# UPX_Port_Adapter.net
KiCad netlist of a schematic drawn in EAGLE
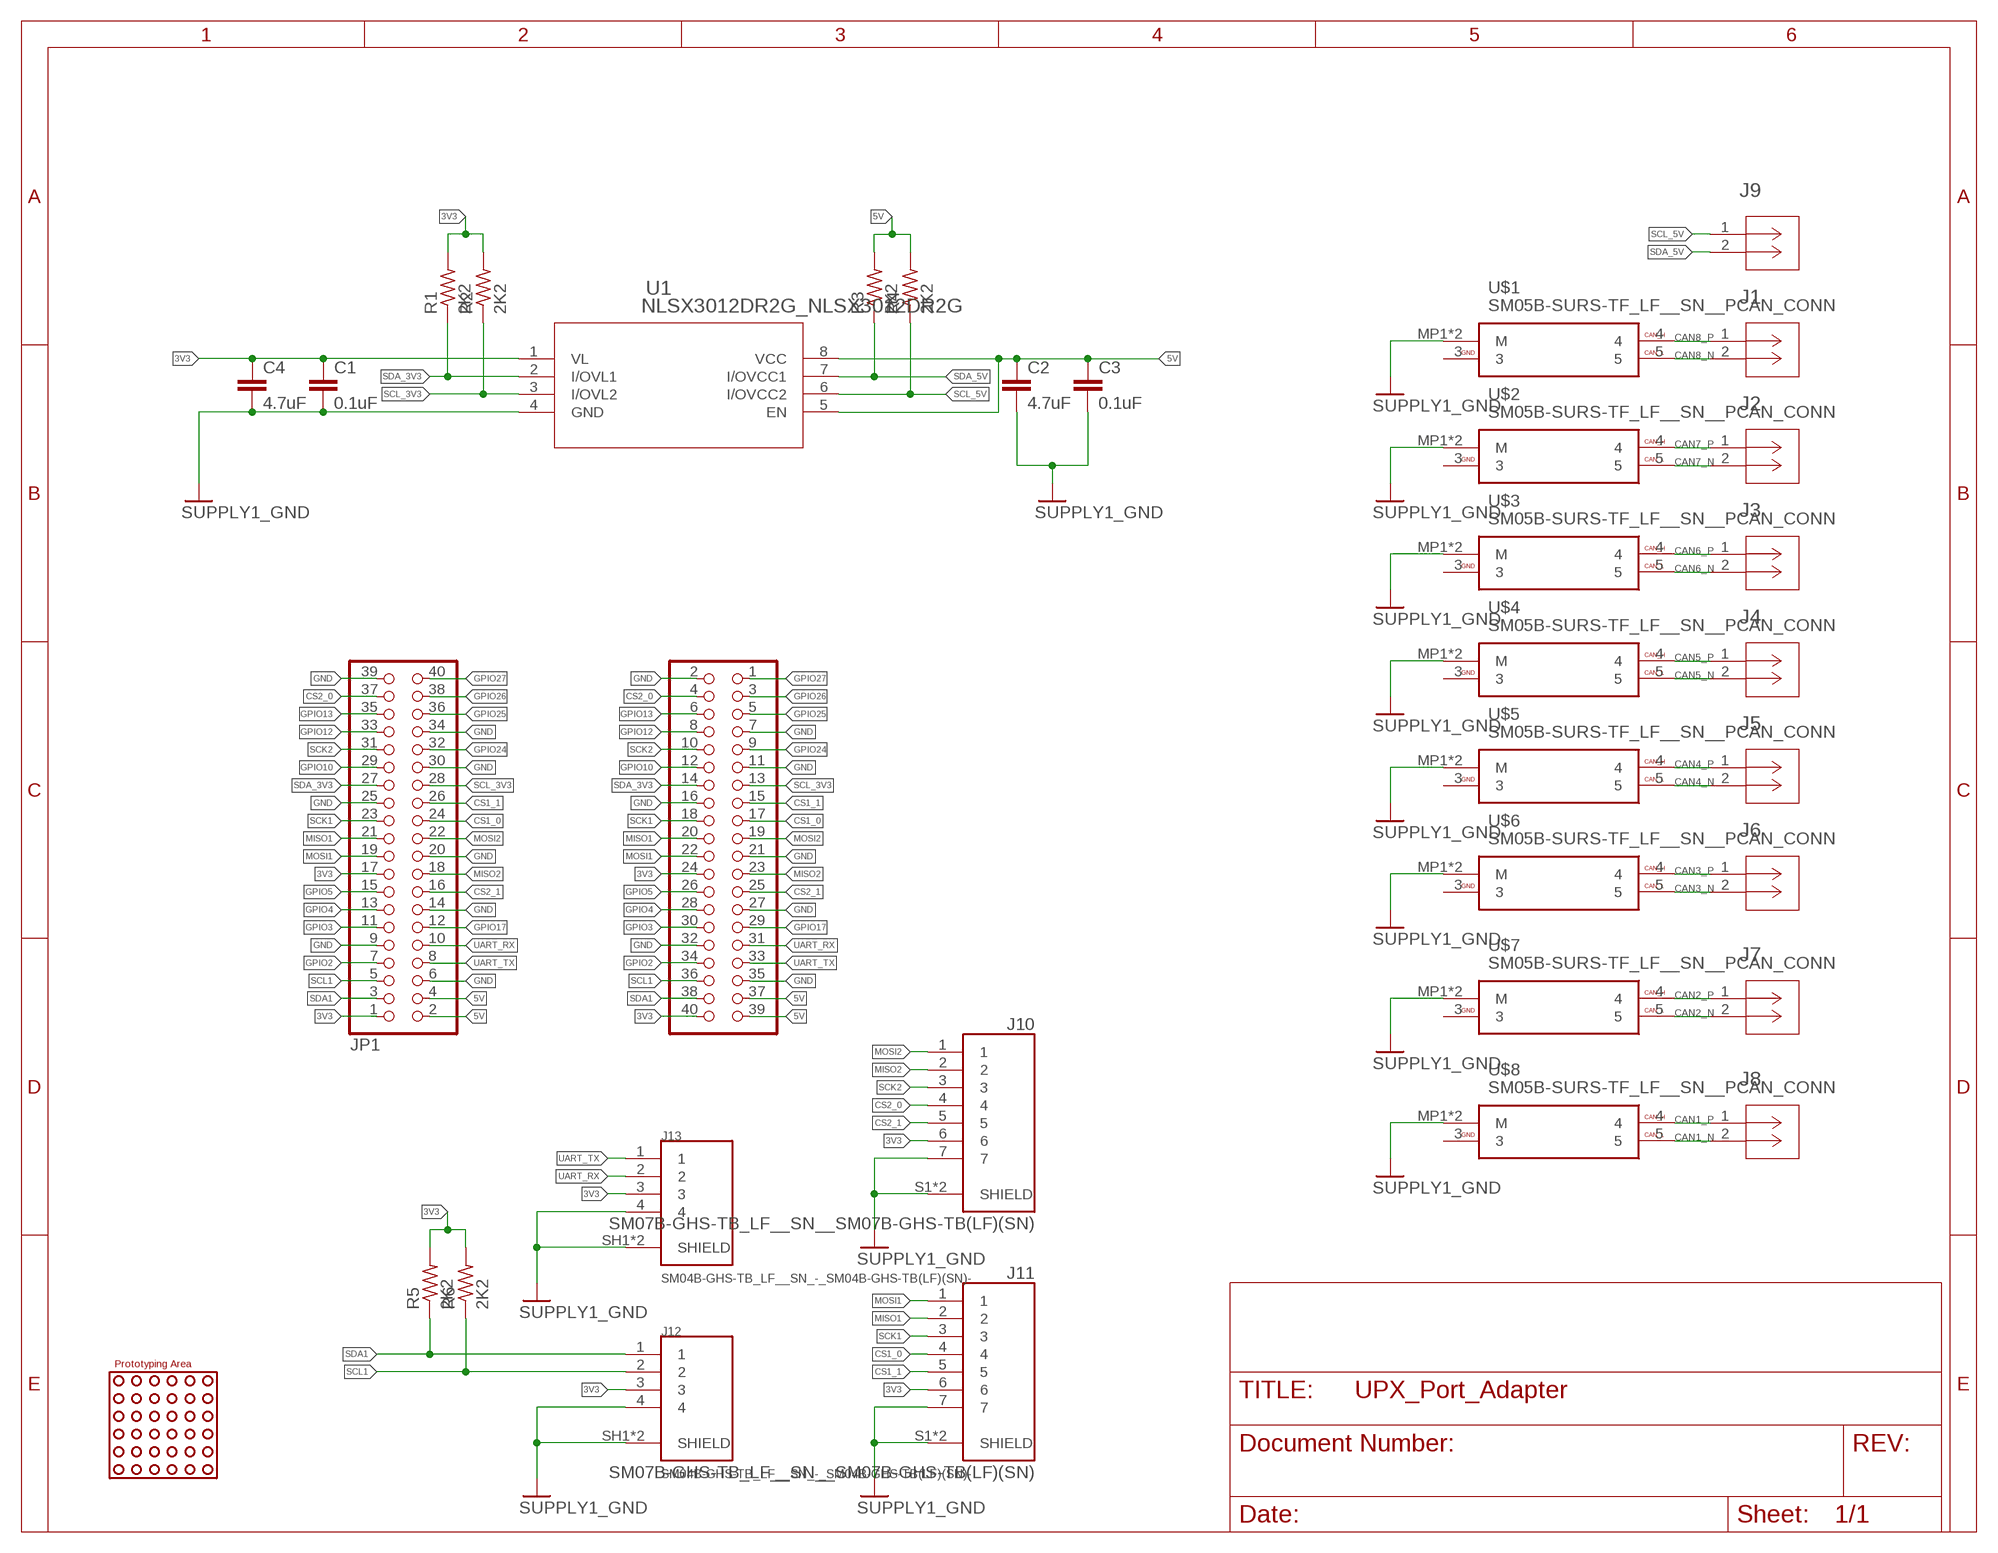
[diagram p0: schematic, sheet 1]

(export (version "E")
  (design (tool "Eeschema 10.0.6"))
  (components
    (comp (ref "C1")
      (value "0.1uF")
      (footprint "eagle-import:RCL_C0603")
      (libsource (lib "eagle-import") (part "RCL_C-EUC0603"))
    )
    (comp (ref "C2")
      (value "4.7uF")
      (footprint "eagle-import:RCL_C0603")
      (libsource (lib "eagle-import") (part "RCL_C-EUC0603"))
    )
    (comp (ref "C3")
      (value "0.1uF")
      (footprint "eagle-import:RCL_C0603")
      (libsource (lib "eagle-import") (part "RCL_C-EUC0603"))
    )
    (comp (ref "C4")
      (value "4.7uF")
      (footprint "eagle-import:RCL_C0603")
      (libsource (lib "eagle-import") (part "RCL_C-EUC0603"))
    )
    (comp (ref "J1")
      (value "SM02B-GHS-TB_SM02BGHSTBLFSN")
      (footprint "eagle-import:SM02B-GHS-TB_CONN_SM02BGHSTB_JST")
      (fields
        (field (name "MANUFACTURER_PART_NUMBER") "SM02BGHSTBLFSN")
        (field (name "COPYRIGHT") "Copyright (C) 2022 Ultra Librarian. All rights reserved.")
      )
      (libsource (lib "eagle-import") (part "SM02B-GHS-TB_SM02BGHSTBLFSN"))
    )
    (comp (ref "J2")
      (value "SM02B-GHS-TB_SM02BGHSTBLFSN")
      (footprint "eagle-import:SM02B-GHS-TB_CONN_SM02BGHSTB_JST")
      (fields
        (field (name "MANUFACTURER_PART_NUMBER") "SM02BGHSTBLFSN")
        (field (name "COPYRIGHT") "Copyright (C) 2022 Ultra Librarian. All rights reserved.")
      )
      (libsource (lib "eagle-import") (part "SM02B-GHS-TB_SM02BGHSTBLFSN"))
    )
    (comp (ref "J3")
      (value "SM02B-GHS-TB_SM02BGHSTBLFSN")
      (footprint "eagle-import:SM02B-GHS-TB_CONN_SM02BGHSTB_JST")
      (fields
        (field (name "MANUFACTURER_PART_NUMBER") "SM02BGHSTBLFSN")
        (field (name "COPYRIGHT") "Copyright (C) 2022 Ultra Librarian. All rights reserved.")
      )
      (libsource (lib "eagle-import") (part "SM02B-GHS-TB_SM02BGHSTBLFSN"))
    )
    (comp (ref "J4")
      (value "SM02B-GHS-TB_SM02BGHSTBLFSN")
      (footprint "eagle-import:SM02B-GHS-TB_CONN_SM02BGHSTB_JST")
      (fields
        (field (name "MANUFACTURER_PART_NUMBER") "SM02BGHSTBLFSN")
        (field (name "COPYRIGHT") "Copyright (C) 2022 Ultra Librarian. All rights reserved.")
      )
      (libsource (lib "eagle-import") (part "SM02B-GHS-TB_SM02BGHSTBLFSN"))
    )
    (comp (ref "J5")
      (value "SM02B-GHS-TB_SM02BGHSTBLFSN")
      (footprint "eagle-import:SM02B-GHS-TB_CONN_SM02BGHSTB_JST")
      (fields
        (field (name "MANUFACTURER_PART_NUMBER") "SM02BGHSTBLFSN")
        (field (name "COPYRIGHT") "Copyright (C) 2022 Ultra Librarian. All rights reserved.")
      )
      (libsource (lib "eagle-import") (part "SM02B-GHS-TB_SM02BGHSTBLFSN"))
    )
    (comp (ref "J6")
      (value "SM02B-GHS-TB_SM02BGHSTBLFSN")
      (footprint "eagle-import:SM02B-GHS-TB_CONN_SM02BGHSTB_JST")
      (fields
        (field (name "MANUFACTURER_PART_NUMBER") "SM02BGHSTBLFSN")
        (field (name "COPYRIGHT") "Copyright (C) 2022 Ultra Librarian. All rights reserved.")
      )
      (libsource (lib "eagle-import") (part "SM02B-GHS-TB_SM02BGHSTBLFSN"))
    )
    (comp (ref "J7")
      (value "SM02B-GHS-TB_SM02BGHSTBLFSN")
      (footprint "eagle-import:SM02B-GHS-TB_CONN_SM02BGHSTB_JST")
      (fields
        (field (name "MANUFACTURER_PART_NUMBER") "SM02BGHSTBLFSN")
        (field (name "COPYRIGHT") "Copyright (C) 2022 Ultra Librarian. All rights reserved.")
      )
      (libsource (lib "eagle-import") (part "SM02B-GHS-TB_SM02BGHSTBLFSN"))
    )
    (comp (ref "J8")
      (value "SM02B-GHS-TB_SM02BGHSTBLFSN")
      (footprint "eagle-import:SM02B-GHS-TB_CONN_SM02BGHSTB_JST")
      (fields
        (field (name "MANUFACTURER_PART_NUMBER") "SM02BGHSTBLFSN")
        (field (name "COPYRIGHT") "Copyright (C) 2022 Ultra Librarian. All rights reserved.")
      )
      (libsource (lib "eagle-import") (part "SM02B-GHS-TB_SM02BGHSTBLFSN"))
    )
    (comp (ref "J9")
      (value "SM02B-GHS-TB_SM02BGHSTBLFSN")
      (footprint "eagle-import:SM02B-GHS-TB_CONN_SM02BGHSTB_JST")
      (fields
        (field (name "MANUFACTURER_PART_NUMBER") "SM02BGHSTBLFSN")
        (field (name "COPYRIGHT") "Copyright (C) 2022 Ultra Librarian. All rights reserved.")
      )
      (libsource (lib "eagle-import") (part "SM02B-GHS-TB_SM02BGHSTBLFSN"))
    )
    (comp (ref "J10")
      (value "SM07B-GHS-TB_LF__SN__SM07B-GHS-TB(LF)(SN)")
      (footprint "eagle-import:SM07B-GHS-TB_LF__SN__JST_SM07B-GHS-TB(LF)(SN)")
      (fields
        (field (name "DIGI-KEY_PART_NUMBER") "455-1569-2-ND")
        (field (name "MF") "JST Sales")
        (field (name "MP") "SM07B-GHS-TB(LF)(SN)")
      )
      (libsource (lib "eagle-import") (part "SM07B-GHS-TB_LF__SN__SM07B-GHS-TB(LF)(SN)"))
    )
    (comp (ref "J11")
      (value "SM07B-GHS-TB_LF__SN__SM07B-GHS-TB(LF)(SN)")
      (footprint "eagle-import:SM07B-GHS-TB_LF__SN__JST_SM07B-GHS-TB(LF)(SN)")
      (fields
        (field (name "DIGI-KEY_PART_NUMBER") "455-1569-2-ND")
        (field (name "MF") "JST Sales")
        (field (name "MP") "SM07B-GHS-TB(LF)(SN)")
      )
      (libsource (lib "eagle-import") (part "SM07B-GHS-TB_LF__SN__SM07B-GHS-TB(LF)(SN)"))
    )
    (comp (ref "J12")
      (value "SM04B-GHS-TB_LF__SN_-_SM04B-GHS-TB(LF)(SN)-")
      (footprint "eagle-import:SM04B-GHS-TB_LF__SN_-_JST_SM04B-GHS-TB(LF)(SN)-")
      (fields
        (field (name "DIGI-KEY_PART_NUMBER") "455-1566-2-ND")
        (field (name "MF") "JST Sales")
        (field (name "MP") "SM04B-GHS-TB(LF)(SN)-")
      )
      (libsource (lib "eagle-import") (part "SM04B-GHS-TB_LF__SN_-_SM04B-GHS-TB(LF)(SN)-"))
    )
    (comp (ref "J13")
      (value "SM04B-GHS-TB_LF__SN_-_SM04B-GHS-TB(LF)(SN)-")
      (footprint "eagle-import:SM04B-GHS-TB_LF__SN_-_JST_SM04B-GHS-TB(LF)(SN)-")
      (fields
        (field (name "DIGI-KEY_PART_NUMBER") "455-1566-2-ND")
        (field (name "MF") "JST Sales")
        (field (name "MP") "SM04B-GHS-TB(LF)(SN)-")
      )
      (libsource (lib "eagle-import") (part "SM04B-GHS-TB_LF__SN_-_SM04B-GHS-TB(LF)(SN)-"))
    )
    (comp (ref "JP1")
      (value "PINHEAD_PINHD-2X20")
      (footprint "eagle-import:PINHEAD_2X20")
      (libsource (lib "eagle-import") (part "PINHEAD_PINHD-2X20"))
    )
    (comp (ref "JP2")
      (value "PINHEAD2_PINHD-2X20/90:1")
      (footprint "eagle-import:PINHEAD2_2X20_90")
      (libsource (lib "eagle-import") (part "PINHEAD2_PINHD-2X20?{colon}1/90"))
    )
    (comp (ref "R1")
      (value "2K2")
      (footprint "eagle-import:RCL_R0603")
      (libsource (lib "eagle-import") (part "RCL_R-US_R0603"))
    )
    (comp (ref "R2")
      (value "2K2")
      (footprint "eagle-import:RCL_R0603")
      (libsource (lib "eagle-import") (part "RCL_R-US_R0603"))
    )
    (comp (ref "R3")
      (value "2K2")
      (footprint "eagle-import:RCL_R0603")
      (libsource (lib "eagle-import") (part "RCL_R-US_R0603"))
    )
    (comp (ref "R4")
      (value "2K2")
      (footprint "eagle-import:RCL_R0603")
      (libsource (lib "eagle-import") (part "RCL_R-US_R0603"))
    )
    (comp (ref "R5")
      (value "2K2")
      (footprint "eagle-import:RCL_R0603")
      (libsource (lib "eagle-import") (part "RCL_R-US_R0603"))
    )
    (comp (ref "R6")
      (value "2K2")
      (footprint "eagle-import:RCL_R0603")
      (libsource (lib "eagle-import") (part "RCL_R-US_R0603"))
    )
    (comp (ref "U$1")
      (value "SM05B-SURS-TF_LF__SN__PCAN_CONN")
      (footprint "eagle-import:SM05B-SURS-TF_LF__SN__SM05BSURSTFLFSN")
      (libsource (lib "eagle-import") (part "SM05B-SURS-TF_LF__SN__PCAN_CONN"))
    )
    (comp (ref "U$2")
      (value "SM05B-SURS-TF_LF__SN__PCAN_CONN")
      (footprint "eagle-import:SM05B-SURS-TF_LF__SN__SM05BSURSTFLFSN")
      (libsource (lib "eagle-import") (part "SM05B-SURS-TF_LF__SN__PCAN_CONN"))
    )
    (comp (ref "U$3")
      (value "SM05B-SURS-TF_LF__SN__PCAN_CONN")
      (footprint "eagle-import:SM05B-SURS-TF_LF__SN__SM05BSURSTFLFSN")
      (libsource (lib "eagle-import") (part "SM05B-SURS-TF_LF__SN__PCAN_CONN"))
    )
    (comp (ref "U$4")
      (value "SM05B-SURS-TF_LF__SN__PCAN_CONN")
      (footprint "eagle-import:SM05B-SURS-TF_LF__SN__SM05BSURSTFLFSN")
      (libsource (lib "eagle-import") (part "SM05B-SURS-TF_LF__SN__PCAN_CONN"))
    )
    (comp (ref "U$5")
      (value "SM05B-SURS-TF_LF__SN__PCAN_CONN")
      (footprint "eagle-import:SM05B-SURS-TF_LF__SN__SM05BSURSTFLFSN")
      (libsource (lib "eagle-import") (part "SM05B-SURS-TF_LF__SN__PCAN_CONN"))
    )
    (comp (ref "U$6")
      (value "SM05B-SURS-TF_LF__SN__PCAN_CONN")
      (footprint "eagle-import:SM05B-SURS-TF_LF__SN__SM05BSURSTFLFSN")
      (libsource (lib "eagle-import") (part "SM05B-SURS-TF_LF__SN__PCAN_CONN"))
    )
    (comp (ref "U$7")
      (value "SM05B-SURS-TF_LF__SN__PCAN_CONN")
      (footprint "eagle-import:SM05B-SURS-TF_LF__SN__SM05BSURSTFLFSN")
      (libsource (lib "eagle-import") (part "SM05B-SURS-TF_LF__SN__PCAN_CONN"))
    )
    (comp (ref "U$8")
      (value "SM05B-SURS-TF_LF__SN__PCAN_CONN")
      (footprint "eagle-import:SM05B-SURS-TF_LF__SN__SM05BSURSTFLFSN")
      (libsource (lib "eagle-import") (part "SM05B-SURS-TF_LF__SN__PCAN_CONN"))
    )
    (comp (ref "U$9")
      (value "PINHEAD-CUSTOM_20X20")
      (footprint "eagle-import:PINHEAD-CUSTOM_20X20")
      (libsource (lib "eagle-import") (part "PINHEAD-CUSTOM_20X20"))
    )
    (comp (ref "U1")
      (value "NLSX3012DR2G_NLSX3012DR2G")
      (footprint "eagle-import:NLSX3012DR2G_SOIC-8_NB_ONS")
      (fields
        (field (name "MANUFACTURER_PART_NUMBER") "NLSX3012DR2G")
        (field (name "COPYRIGHT") "Copyright (C) 2022 Ultra Librarian. All rights reserved.")
      )
      (libsource (lib "eagle-import") (part "NLSX3012DR2G_NLSX3012DR2G"))
    )
  )
  (nets
    (net (code "1") (name "/CAN1_N") (class "Default")
      (node (ref "J8") (pin "2") (pinfunction "2_2") (pintype "passive"))
      (node (ref "U$8") (pin "5") (pinfunction "5_5") (pintype "bidirectional"))
    )
    (net (code "2") (name "/CAN1_P") (class "Default")
      (node (ref "J8") (pin "1") (pinfunction "1_1") (pintype "passive"))
      (node (ref "U$8") (pin "4") (pinfunction "4_4") (pintype "bidirectional"))
    )
    (net (code "3") (name "/CAN2_N") (class "Default")
      (node (ref "J7") (pin "2") (pinfunction "2_2") (pintype "passive"))
      (node (ref "U$7") (pin "5") (pinfunction "5_5") (pintype "bidirectional"))
    )
    (net (code "4") (name "/CAN2_P") (class "Default")
      (node (ref "J7") (pin "1") (pinfunction "1_1") (pintype "passive"))
      (node (ref "U$7") (pin "4") (pinfunction "4_4") (pintype "bidirectional"))
    )
    (net (code "5") (name "/CAN3_N") (class "Default")
      (node (ref "J6") (pin "2") (pinfunction "2_2") (pintype "passive"))
      (node (ref "U$6") (pin "5") (pinfunction "5_5") (pintype "bidirectional"))
    )
    (net (code "6") (name "/CAN3_P") (class "Default")
      (node (ref "J6") (pin "1") (pinfunction "1_1") (pintype "passive"))
      (node (ref "U$6") (pin "4") (pinfunction "4_4") (pintype "bidirectional"))
    )
    (net (code "7") (name "/CAN4_N") (class "Default")
      (node (ref "J5") (pin "2") (pinfunction "2_2") (pintype "passive"))
      (node (ref "U$5") (pin "5") (pinfunction "5_5") (pintype "bidirectional"))
    )
    (net (code "8") (name "/CAN4_P") (class "Default")
      (node (ref "J5") (pin "1") (pinfunction "1_1") (pintype "passive"))
      (node (ref "U$5") (pin "4") (pinfunction "4_4") (pintype "bidirectional"))
    )
    (net (code "9") (name "/CAN5_N") (class "Default")
      (node (ref "J4") (pin "2") (pinfunction "2_2") (pintype "passive"))
      (node (ref "U$4") (pin "5") (pinfunction "5_5") (pintype "bidirectional"))
    )
    (net (code "10") (name "/CAN5_P") (class "Default")
      (node (ref "J4") (pin "1") (pinfunction "1_1") (pintype "passive"))
      (node (ref "U$4") (pin "4") (pinfunction "4_4") (pintype "bidirectional"))
    )
    (net (code "11") (name "/CAN6_N") (class "Default")
      (node (ref "J3") (pin "2") (pinfunction "2_2") (pintype "passive"))
      (node (ref "U$3") (pin "5") (pinfunction "5_5") (pintype "bidirectional"))
    )
    (net (code "12") (name "/CAN6_P") (class "Default")
      (node (ref "J3") (pin "1") (pinfunction "1_1") (pintype "passive"))
      (node (ref "U$3") (pin "4") (pinfunction "4_4") (pintype "bidirectional"))
    )
    (net (code "13") (name "/CAN7_N") (class "Default")
      (node (ref "J2") (pin "2") (pinfunction "2_2") (pintype "passive"))
      (node (ref "U$2") (pin "5") (pinfunction "5_5") (pintype "bidirectional"))
    )
    (net (code "14") (name "/CAN7_P") (class "Default")
      (node (ref "J2") (pin "1") (pinfunction "1_1") (pintype "passive"))
      (node (ref "U$2") (pin "4") (pinfunction "4_4") (pintype "bidirectional"))
    )
    (net (code "15") (name "/CAN8_N") (class "Default")
      (node (ref "J1") (pin "2") (pinfunction "2_2") (pintype "passive"))
      (node (ref "U$1") (pin "5") (pinfunction "5_5") (pintype "bidirectional"))
    )
    (net (code "16") (name "/CAN8_P") (class "Default")
      (node (ref "J1") (pin "1") (pinfunction "1_1") (pintype "passive"))
      (node (ref "U$1") (pin "4") (pinfunction "4_4") (pintype "bidirectional"))
    )
    (net (code "17") (name "3V3") (class "Default")
      (node (ref "C1") (pin "1") (pinfunction "1_1") (pintype "passive"))
      (node (ref "C4") (pin "1") (pinfunction "1_1") (pintype "passive"))
      (node (ref "J10") (pin "6") (pinfunction "6_6") (pintype "passive"))
      (node (ref "J11") (pin "6") (pinfunction "6_6") (pintype "passive"))
      (node (ref "J12") (pin "3") (pinfunction "3_3") (pintype "passive"))
      (node (ref "J13") (pin "3") (pinfunction "3_3") (pintype "passive"))
      (node (ref "JP1") (pin "1") (pinfunction "1_1") (pintype "passive"))
      (node (ref "JP1") (pin "17") (pinfunction "17_17") (pintype "passive"))
      (node (ref "JP2") (pin "24") (pinfunction "24_24") (pintype "passive"))
      (node (ref "JP2") (pin "40") (pinfunction "40_40") (pintype "passive"))
      (node (ref "R1") (pin "2") (pinfunction "2_2") (pintype "passive"))
      (node (ref "R2") (pin "2") (pinfunction "2_2") (pintype "passive"))
      (node (ref "R5") (pin "2") (pinfunction "2_2") (pintype "passive"))
      (node (ref "R6") (pin "2") (pinfunction "2_2") (pintype "passive"))
      (node (ref "U1") (pin "1") (pinfunction "VL_1") (pintype "input"))
    )
    (net (code "18") (name "5V") (class "Default")
      (node (ref "C2") (pin "1") (pinfunction "1_1") (pintype "passive"))
      (node (ref "C3") (pin "1") (pinfunction "1_1") (pintype "passive"))
      (node (ref "JP1") (pin "2") (pinfunction "2_2") (pintype "passive"))
      (node (ref "JP1") (pin "4") (pinfunction "4_4") (pintype "passive"))
      (node (ref "JP2") (pin "37") (pinfunction "37_37") (pintype "passive"))
      (node (ref "JP2") (pin "39") (pinfunction "39_39") (pintype "passive"))
      (node (ref "R3") (pin "2") (pinfunction "2_2") (pintype "passive"))
      (node (ref "R4") (pin "2") (pinfunction "2_2") (pintype "passive"))
      (node (ref "U1") (pin "5") (pinfunction "EN_5") (pintype "output"))
      (node (ref "U1") (pin "8") (pinfunction "VCC_8") (pintype "power_in"))
    )
    (net (code "19") (name "CS1_0") (class "Default")
      (node (ref "J11") (pin "4") (pinfunction "4_4") (pintype "passive"))
      (node (ref "JP1") (pin "24") (pinfunction "24_24") (pintype "passive"))
      (node (ref "JP2") (pin "17") (pinfunction "17_17") (pintype "passive"))
    )
    (net (code "20") (name "CS1_1") (class "Default")
      (node (ref "J11") (pin "5") (pinfunction "5_5") (pintype "passive"))
      (node (ref "JP1") (pin "26") (pinfunction "26_26") (pintype "passive"))
      (node (ref "JP2") (pin "15") (pinfunction "15_15") (pintype "passive"))
    )
    (net (code "21") (name "CS2_0") (class "Default")
      (node (ref "J10") (pin "4") (pinfunction "4_4") (pintype "passive"))
      (node (ref "JP1") (pin "37") (pinfunction "37_37") (pintype "passive"))
      (node (ref "JP2") (pin "4") (pinfunction "4_4") (pintype "passive"))
    )
    (net (code "22") (name "CS2_1") (class "Default")
      (node (ref "J10") (pin "5") (pinfunction "5_5") (pintype "passive"))
      (node (ref "JP1") (pin "16") (pinfunction "16_16") (pintype "passive"))
      (node (ref "JP2") (pin "25") (pinfunction "25_25") (pintype "passive"))
    )
    (net (code "23") (name "GND") (class "Default")
      (node (ref "C1") (pin "2") (pinfunction "2_2") (pintype "passive"))
      (node (ref "C2") (pin "2") (pinfunction "2_2") (pintype "passive"))
      (node (ref "C3") (pin "2") (pinfunction "2_2") (pintype "passive"))
      (node (ref "C4") (pin "2") (pinfunction "2_2") (pintype "passive"))
      (node (ref "J10") (pin "7") (pinfunction "7_7") (pintype "passive"))
      (node (ref "J10") (pin "S1") (pinfunction "SHIELD_S1") (pintype "power_in"))
      (node (ref "J10") (pin "S2") (pinfunction "SHIELD_S2") (pintype "power_in"))
      (node (ref "J11") (pin "7") (pinfunction "7_7") (pintype "passive"))
      (node (ref "J11") (pin "S1") (pinfunction "SHIELD_S1") (pintype "power_in"))
      (node (ref "J11") (pin "S2") (pinfunction "SHIELD_S2") (pintype "power_in"))
      (node (ref "J12") (pin "4") (pinfunction "4_4") (pintype "passive"))
      (node (ref "J12") (pin "SH1") (pinfunction "SHIELD_SH1") (pintype "power_in"))
      (node (ref "J12") (pin "SH2") (pinfunction "SHIELD_SH2") (pintype "power_in"))
      (node (ref "J13") (pin "4") (pinfunction "4_4") (pintype "passive"))
      (node (ref "J13") (pin "SH1") (pinfunction "SHIELD_SH1") (pintype "power_in"))
      (node (ref "J13") (pin "SH2") (pinfunction "SHIELD_SH2") (pintype "power_in"))
      (node (ref "JP1") (pin "14") (pinfunction "14_14") (pintype "passive"))
      (node (ref "JP1") (pin "20") (pinfunction "20_20") (pintype "passive"))
      (node (ref "JP1") (pin "25") (pinfunction "25_25") (pintype "passive"))
      (node (ref "JP1") (pin "30") (pinfunction "30_30") (pintype "passive"))
      (node (ref "JP1") (pin "34") (pinfunction "34_34") (pintype "passive"))
      (node (ref "JP1") (pin "39") (pinfunction "39_39") (pintype "passive"))
      (node (ref "JP1") (pin "6") (pinfunction "6_6") (pintype "passive"))
      (node (ref "JP1") (pin "9") (pinfunction "9_9") (pintype "passive"))
      (node (ref "JP2") (pin "11") (pinfunction "11_11") (pintype "passive"))
      (node (ref "JP2") (pin "16") (pinfunction "16_16") (pintype "passive"))
      (node (ref "JP2") (pin "2") (pinfunction "2_2") (pintype "passive"))
      (node (ref "JP2") (pin "21") (pinfunction "21_21") (pintype "passive"))
      (node (ref "JP2") (pin "27") (pinfunction "27_27") (pintype "passive"))
      (node (ref "JP2") (pin "32") (pinfunction "32_32") (pintype "passive"))
      (node (ref "JP2") (pin "35") (pinfunction "35_35") (pintype "passive"))
      (node (ref "JP2") (pin "7") (pinfunction "7_7") (pintype "passive"))
      (node (ref "U$1") (pin "MP1") (pinfunction "M_MP1") (pintype "bidirectional"))
      (node (ref "U$1") (pin "MP2") (pinfunction "M_MP2") (pintype "bidirectional"))
      (node (ref "U$2") (pin "MP1") (pinfunction "M_MP1") (pintype "bidirectional"))
      (node (ref "U$2") (pin "MP2") (pinfunction "M_MP2") (pintype "bidirectional"))
      (node (ref "U$3") (pin "MP1") (pinfunction "M_MP1") (pintype "bidirectional"))
      (node (ref "U$3") (pin "MP2") (pinfunction "M_MP2") (pintype "bidirectional"))
      (node (ref "U$4") (pin "MP1") (pinfunction "M_MP1") (pintype "bidirectional"))
      (node (ref "U$4") (pin "MP2") (pinfunction "M_MP2") (pintype "bidirectional"))
      (node (ref "U$5") (pin "MP1") (pinfunction "M_MP1") (pintype "bidirectional"))
      (node (ref "U$5") (pin "MP2") (pinfunction "M_MP2") (pintype "bidirectional"))
      (node (ref "U$6") (pin "MP1") (pinfunction "M_MP1") (pintype "bidirectional"))
      (node (ref "U$6") (pin "MP2") (pinfunction "M_MP2") (pintype "bidirectional"))
      (node (ref "U$7") (pin "MP1") (pinfunction "M_MP1") (pintype "bidirectional"))
      (node (ref "U$7") (pin "MP2") (pinfunction "M_MP2") (pintype "bidirectional"))
      (node (ref "U$8") (pin "MP1") (pinfunction "M_MP1") (pintype "bidirectional"))
      (node (ref "U$8") (pin "MP2") (pinfunction "M_MP2") (pintype "bidirectional"))
      (node (ref "U1") (pin "4") (pinfunction "GND_4") (pintype "power_in"))
    )
    (net (code "24") (name "GPIO2") (class "Default")
      (node (ref "JP1") (pin "7") (pinfunction "7_7") (pintype "passive"))
      (node (ref "JP2") (pin "34") (pinfunction "34_34") (pintype "passive"))
    )
    (net (code "25") (name "GPIO3") (class "Default")
      (node (ref "JP1") (pin "11") (pinfunction "11_11") (pintype "passive"))
      (node (ref "JP2") (pin "30") (pinfunction "30_30") (pintype "passive"))
    )
    (net (code "26") (name "GPIO4") (class "Default")
      (node (ref "JP1") (pin "13") (pinfunction "13_13") (pintype "passive"))
      (node (ref "JP2") (pin "28") (pinfunction "28_28") (pintype "passive"))
    )
    (net (code "27") (name "GPIO5") (class "Default")
      (node (ref "JP1") (pin "15") (pinfunction "15_15") (pintype "passive"))
      (node (ref "JP2") (pin "26") (pinfunction "26_26") (pintype "passive"))
    )
    (net (code "28") (name "GPIO10") (class "Default")
      (node (ref "JP1") (pin "29") (pinfunction "29_29") (pintype "passive"))
      (node (ref "JP2") (pin "12") (pinfunction "12_12") (pintype "passive"))
    )
    (net (code "29") (name "GPIO12") (class "Default")
      (node (ref "JP1") (pin "33") (pinfunction "33_33") (pintype "passive"))
      (node (ref "JP2") (pin "8") (pinfunction "8_8") (pintype "passive"))
    )
    (net (code "30") (name "GPIO13") (class "Default")
      (node (ref "JP1") (pin "35") (pinfunction "35_35") (pintype "passive"))
      (node (ref "JP2") (pin "6") (pinfunction "6_6") (pintype "passive"))
    )
    (net (code "31") (name "GPIO17") (class "Default")
      (node (ref "JP1") (pin "12") (pinfunction "12_12") (pintype "passive"))
      (node (ref "JP2") (pin "29") (pinfunction "29_29") (pintype "passive"))
    )
    (net (code "32") (name "GPIO24") (class "Default")
      (node (ref "JP1") (pin "32") (pinfunction "32_32") (pintype "passive"))
      (node (ref "JP2") (pin "9") (pinfunction "9_9") (pintype "passive"))
    )
    (net (code "33") (name "GPIO25") (class "Default")
      (node (ref "JP1") (pin "36") (pinfunction "36_36") (pintype "passive"))
      (node (ref "JP2") (pin "5") (pinfunction "5_5") (pintype "passive"))
    )
    (net (code "34") (name "GPIO26") (class "Default")
      (node (ref "JP1") (pin "38") (pinfunction "38_38") (pintype "passive"))
      (node (ref "JP2") (pin "3") (pinfunction "3_3") (pintype "passive"))
    )
    (net (code "35") (name "GPIO27") (class "Default")
      (node (ref "JP1") (pin "40") (pinfunction "40_40") (pintype "passive"))
      (node (ref "JP2") (pin "1") (pinfunction "1_1") (pintype "passive"))
    )
    (net (code "36") (name "MISO1") (class "Default")
      (node (ref "J11") (pin "2") (pinfunction "2_2") (pintype "passive"))
      (node (ref "JP1") (pin "21") (pinfunction "21_21") (pintype "passive"))
      (node (ref "JP2") (pin "20") (pinfunction "20_20") (pintype "passive"))
    )
    (net (code "37") (name "MISO2") (class "Default")
      (node (ref "J10") (pin "2") (pinfunction "2_2") (pintype "passive"))
      (node (ref "JP1") (pin "18") (pinfunction "18_18") (pintype "passive"))
      (node (ref "JP2") (pin "23") (pinfunction "23_23") (pintype "passive"))
    )
    (net (code "38") (name "MOSI1") (class "Default")
      (node (ref "J11") (pin "1") (pinfunction "1_1") (pintype "passive"))
      (node (ref "JP1") (pin "19") (pinfunction "19_19") (pintype "passive"))
      (node (ref "JP2") (pin "22") (pinfunction "22_22") (pintype "passive"))
    )
    (net (code "39") (name "MOSI2") (class "Default")
      (node (ref "J10") (pin "1") (pinfunction "1_1") (pintype "passive"))
      (node (ref "JP1") (pin "22") (pinfunction "22_22") (pintype "passive"))
      (node (ref "JP2") (pin "19") (pinfunction "19_19") (pintype "passive"))
    )
    (net (code "40") (name "SCK1") (class "Default")
      (node (ref "J11") (pin "3") (pinfunction "3_3") (pintype "passive"))
      (node (ref "JP1") (pin "23") (pinfunction "23_23") (pintype "passive"))
      (node (ref "JP2") (pin "18") (pinfunction "18_18") (pintype "passive"))
    )
    (net (code "41") (name "SCK2") (class "Default")
      (node (ref "J10") (pin "3") (pinfunction "3_3") (pintype "passive"))
      (node (ref "JP1") (pin "31") (pinfunction "31_31") (pintype "passive"))
      (node (ref "JP2") (pin "10") (pinfunction "10_10") (pintype "passive"))
    )
    (net (code "42") (name "SCL1") (class "Default")
      (node (ref "J12") (pin "2") (pinfunction "2_2") (pintype "passive"))
      (node (ref "JP1") (pin "5") (pinfunction "5_5") (pintype "passive"))
      (node (ref "JP2") (pin "36") (pinfunction "36_36") (pintype "passive"))
      (node (ref "R6") (pin "1") (pinfunction "1_1") (pintype "passive"))
    )
    (net (code "43") (name "SCL_3V3") (class "Default")
      (node (ref "JP1") (pin "28") (pinfunction "28_28") (pintype "passive"))
      (node (ref "JP2") (pin "13") (pinfunction "13_13") (pintype "passive"))
      (node (ref "R2") (pin "1") (pinfunction "1_1") (pintype "passive"))
      (node (ref "U1") (pin "3") (pinfunction "I/OVL2_3") (pintype "bidirectional"))
    )
    (net (code "44") (name "SCL_5V") (class "Default")
      (node (ref "J9") (pin "1") (pinfunction "1_1") (pintype "passive"))
      (node (ref "R4") (pin "1") (pinfunction "1_1") (pintype "passive"))
      (node (ref "U1") (pin "6") (pinfunction "I/OVCC2_6") (pintype "bidirectional"))
    )
    (net (code "45") (name "SDA1") (class "Default")
      (node (ref "J12") (pin "1") (pinfunction "1_1") (pintype "passive"))
      (node (ref "JP1") (pin "3") (pinfunction "3_3") (pintype "passive"))
      (node (ref "JP2") (pin "38") (pinfunction "38_38") (pintype "passive"))
      (node (ref "R5") (pin "1") (pinfunction "1_1") (pintype "passive"))
    )
    (net (code "46") (name "SDA_3V3") (class "Default")
      (node (ref "JP1") (pin "27") (pinfunction "27_27") (pintype "passive"))
      (node (ref "JP2") (pin "14") (pinfunction "14_14") (pintype "passive"))
      (node (ref "R1") (pin "1") (pinfunction "1_1") (pintype "passive"))
      (node (ref "U1") (pin "2") (pinfunction "I/OVL1_2") (pintype "bidirectional"))
    )
    (net (code "47") (name "SDA_5V") (class "Default")
      (node (ref "J9") (pin "2") (pinfunction "2_2") (pintype "passive"))
      (node (ref "R3") (pin "1") (pinfunction "1_1") (pintype "passive"))
      (node (ref "U1") (pin "7") (pinfunction "I/OVCC1_7") (pintype "bidirectional"))
    )
    (net (code "48") (name "UART_RX") (class "Default")
      (node (ref "J13") (pin "2") (pinfunction "2_2") (pintype "passive"))
      (node (ref "JP1") (pin "10") (pinfunction "10_10") (pintype "passive"))
      (node (ref "JP2") (pin "31") (pinfunction "31_31") (pintype "passive"))
    )
    (net (code "49") (name "UART_TX") (class "Default")
      (node (ref "J13") (pin "1") (pinfunction "1_1") (pintype "passive"))
      (node (ref "JP1") (pin "8") (pinfunction "8_8") (pintype "passive"))
      (node (ref "JP2") (pin "33") (pinfunction "33_33") (pintype "passive"))
    )
    (net (code "50") (name "unconnected-(U$1-Pad3)") (class "Default")
      (node (ref "U$1") (pin "3") (pinfunction "3_3") (pintype "bidirectional"))
    )
    (net (code "51") (name "unconnected-(U$2-Pad3)") (class "Default")
      (node (ref "U$2") (pin "3") (pinfunction "3_3") (pintype "bidirectional"))
    )
    (net (code "52") (name "unconnected-(U$3-Pad3)") (class "Default")
      (node (ref "U$3") (pin "3") (pinfunction "3_3") (pintype "bidirectional"))
    )
    (net (code "53") (name "unconnected-(U$4-Pad3)") (class "Default")
      (node (ref "U$4") (pin "3") (pinfunction "3_3") (pintype "bidirectional"))
    )
    (net (code "54") (name "unconnected-(U$5-Pad3)") (class "Default")
      (node (ref "U$5") (pin "3") (pinfunction "3_3") (pintype "bidirectional"))
    )
    (net (code "55") (name "unconnected-(U$6-Pad3)") (class "Default")
      (node (ref "U$6") (pin "3") (pinfunction "3_3") (pintype "bidirectional"))
    )
    (net (code "56") (name "unconnected-(U$7-Pad3)") (class "Default")
      (node (ref "U$7") (pin "3") (pinfunction "3_3") (pintype "bidirectional"))
    )
    (net (code "57") (name "unconnected-(U$8-Pad3)") (class "Default")
      (node (ref "U$8") (pin "3") (pinfunction "3_3") (pintype "bidirectional"))
    )
  )
)
